# v1_1_Main.net
KiCad netlist of a schematic drawn in EAGLE
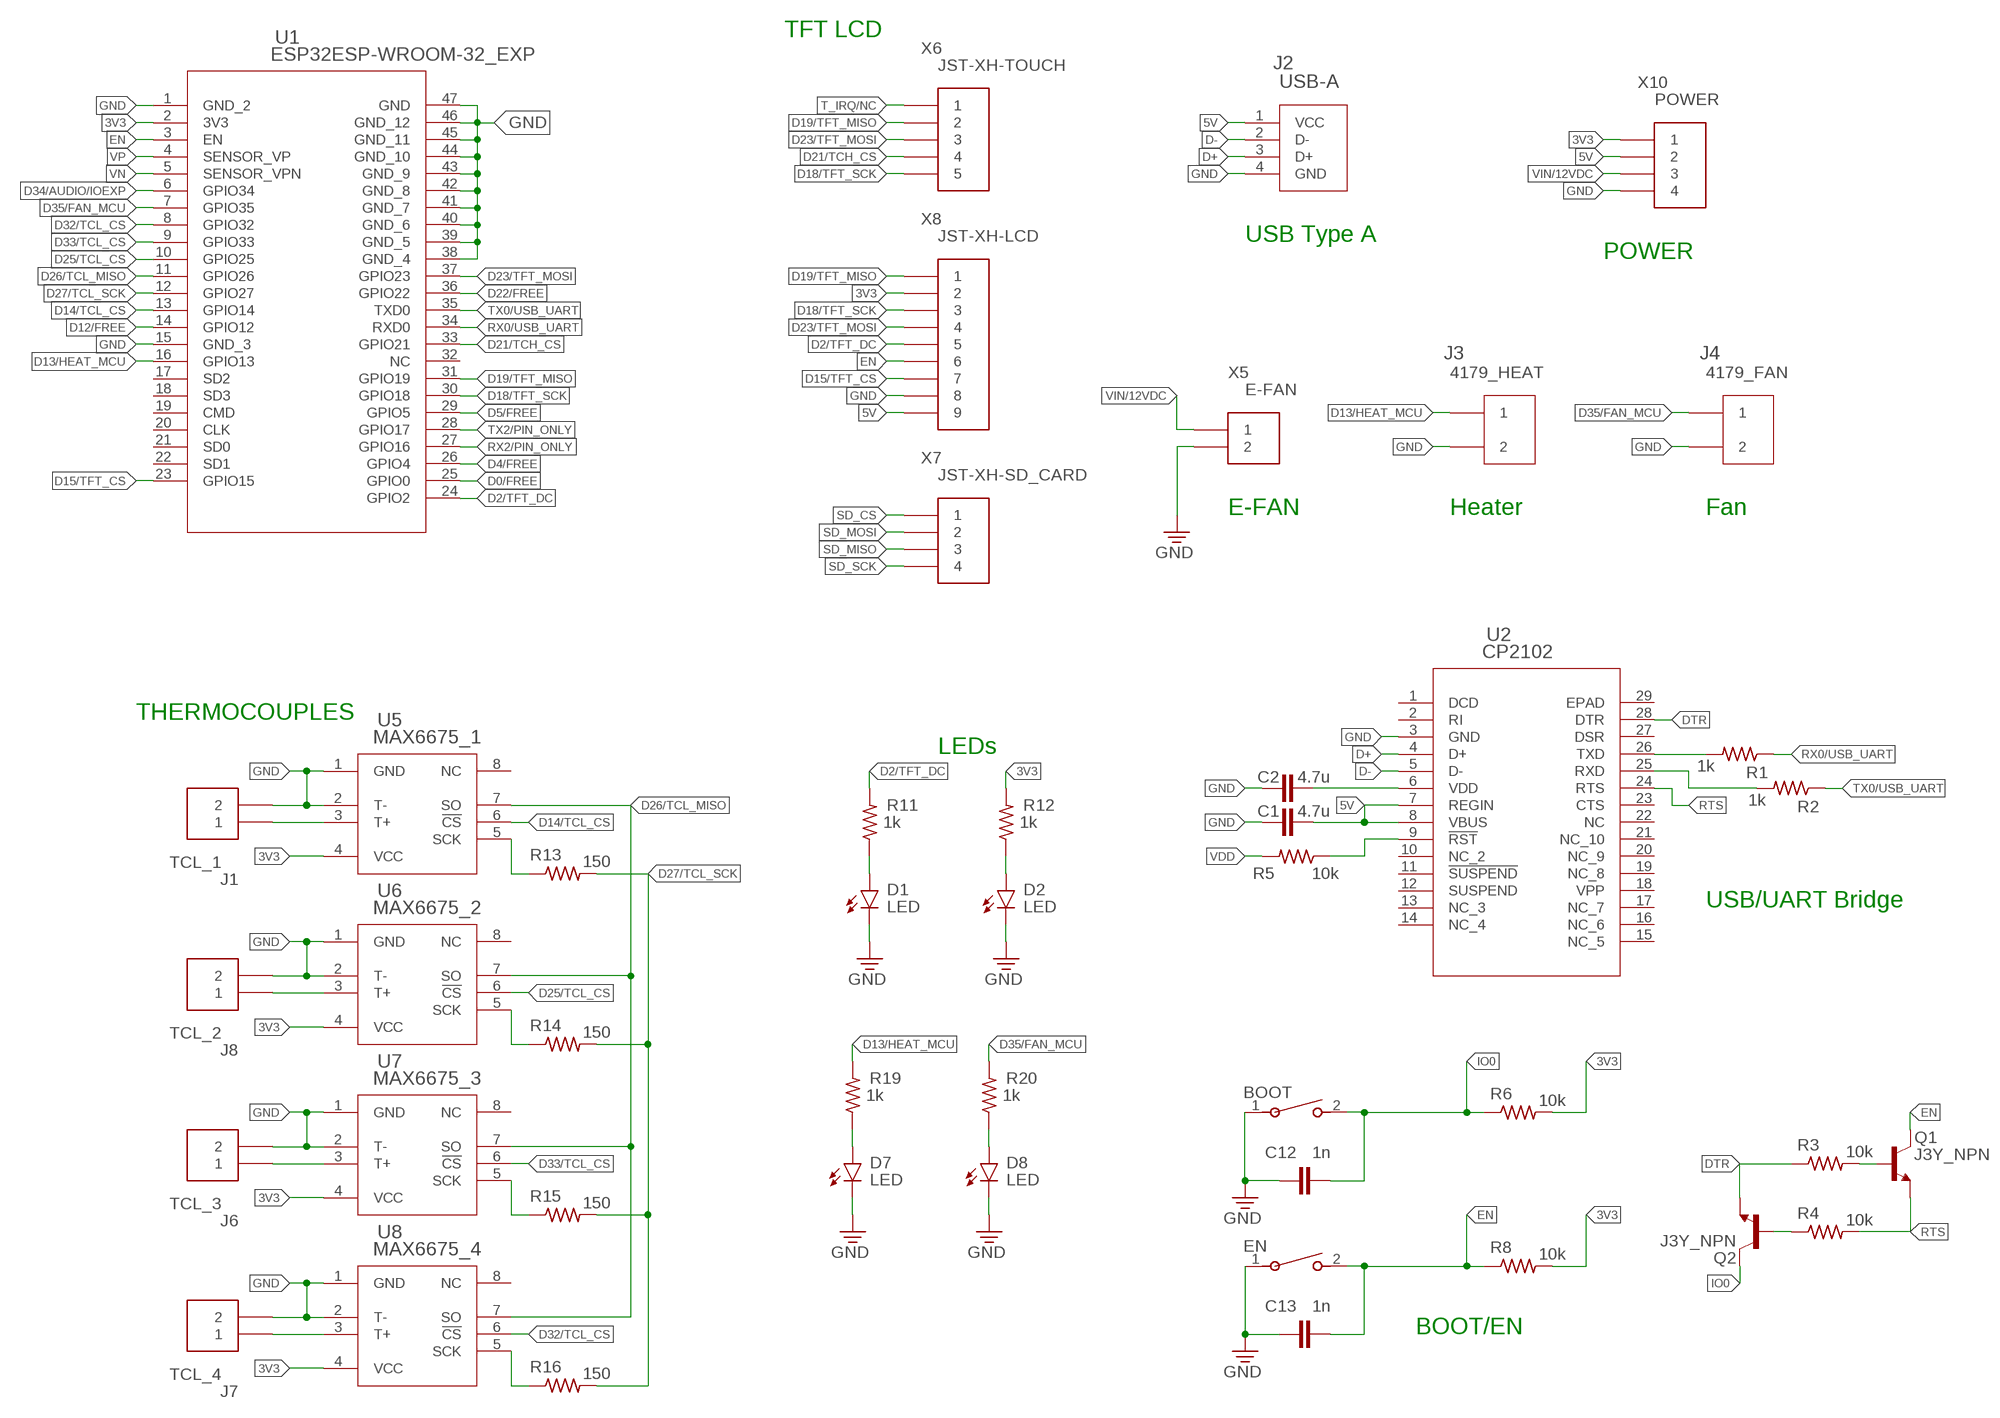
[diagram p0: schematic, sheet 1]

(export (version "E")
  (design (tool "Eeschema 10.0.6"))
  (components
    (comp (ref "BOOT")
      (value "EVQ22705RSW_EVQ22705R_PAN")
      (footprint "eagle-import:SW_EVQ22705R_PAN")
      (fields
        (field (name "MANUFACTURER_PART_NUMBER") "EVQ-22705R")
        (field (name "COPYRIGHT") "Copyright (C) 2024 Ultra Librarian. All rights reserved.")
      )
      (libsource (lib "eagle-import") (part "EVQ22705RSW_EVQ22705R_PAN"))
    )
    (comp (ref "C1")
      (value "4.7u")
      (footprint "eagle-import:CAPC2012X110")
      (libsource (lib "eagle-import") (part "CCHIP-0805(2012-METRIC)_"))
    )
    (comp (ref "C2")
      (value "4.7u")
      (footprint "eagle-import:CAPC2012X110")
      (libsource (lib "eagle-import") (part "CCHIP-0805(2012-METRIC)_"))
    )
    (comp (ref "C12")
      (value "1n")
      (footprint "eagle-import:CAPC2012X110")
      (libsource (lib "eagle-import") (part "CCHIP-0805(2012-METRIC)_"))
    )
    (comp (ref "C13")
      (value "1n")
      (footprint "eagle-import:CAPC2012X110")
      (libsource (lib "eagle-import") (part "CCHIP-0805(2012-METRIC)_"))
    )
    (comp (ref "D1")
      (value "LED")
      (footprint "eagle-import:LEDC2012X110N_FLAT-B")
      (libsource (lib "eagle-import") (part "CHIP-FLAT-B_0805"))
    )
    (comp (ref "D2")
      (value "LED")
      (footprint "eagle-import:LEDC2012X110N_FLAT-B")
      (libsource (lib "eagle-import") (part "CHIP-FLAT-B_0805"))
    )
    (comp (ref "D7")
      (value "LED")
      (footprint "eagle-import:LEDC2012X110N_FLAT-B")
      (libsource (lib "eagle-import") (part "CHIP-FLAT-B_0805"))
    )
    (comp (ref "D8")
      (value "LED")
      (footprint "eagle-import:LEDC2012X110N_FLAT-B")
      (libsource (lib "eagle-import") (part "CHIP-FLAT-B_0805"))
    )
    (comp (ref "EN")
      (value "EVQ22705RSW_EVQ22705R_PAN")
      (footprint "eagle-import:SW_EVQ22705R_PAN")
      (fields
        (field (name "MANUFACTURER_PART_NUMBER") "EVQ-22705R")
        (field (name "COPYRIGHT") "Copyright (C) 2024 Ultra Librarian. All rights reserved.")
      )
      (libsource (lib "eagle-import") (part "EVQ22705RSW_EVQ22705R_PAN"))
    )
    (comp (ref "J1")
      (value "TCL_1")
      (footprint "eagle-import:CONN_OSTVN02A150_OST")
      (fields
        (field (name "MANUFACTURER_PART_NUMBER") "OSTVN02A150")
        (field (name "COPYRIGHT") "Copyright (C) 2025 Ultra Librarian. All rights reserved.")
      )
      (libsource (lib "eagle-import") (part "OSTVN02A150CONN_OSTVN02A150_OST"))
    )
    (comp (ref "J2")
      (value "USB-A")
      (footprint "eagle-import:USB-A")
      (fields
        (field (name "MANUFACTURER_PART_NUMBER") "USB-A1VSB6")
        (field (name "COPYRIGHT") "Copyright (C) 2025 Ultra Librarian. All rights reserved.")
      )
      (libsource (lib "eagle-import") (part "USB-A1VSB6_OST"))
    )
    (comp (ref "J3")
      (value "4179_HEAT")
      (footprint "eagle-import:41791")
      (fields
        (field (name "MANUFACTURER_PART_NUMBER") "417910849")
        (field (name "COPYRIGHT") "Copyright (C) 2025 Ultra Librarian. All rights reserved.")
      )
      (libsource (lib "eagle-import") (part "4179_SDA"))
    )
    (comp (ref "J4")
      (value "4179_FAN")
      (footprint "eagle-import:41791")
      (fields
        (field (name "MANUFACTURER_PART_NUMBER") "417910849")
        (field (name "COPYRIGHT") "Copyright (C) 2025 Ultra Librarian. All rights reserved.")
      )
      (libsource (lib "eagle-import") (part "4179_SDA"))
    )
    (comp (ref "J6")
      (value "TCL_3")
      (footprint "eagle-import:CONN_OSTVN02A150_OST")
      (fields
        (field (name "MANUFACTURER_PART_NUMBER") "OSTVN02A150")
        (field (name "COPYRIGHT") "Copyright (C) 2025 Ultra Librarian. All rights reserved.")
      )
      (libsource (lib "eagle-import") (part "OSTVN02A150CONN_OSTVN02A150_OST"))
    )
    (comp (ref "J7")
      (value "TCL_4")
      (footprint "eagle-import:CONN_OSTVN02A150_OST")
      (fields
        (field (name "MANUFACTURER_PART_NUMBER") "OSTVN02A150")
        (field (name "COPYRIGHT") "Copyright (C) 2025 Ultra Librarian. All rights reserved.")
      )
      (libsource (lib "eagle-import") (part "OSTVN02A150CONN_OSTVN02A150_OST"))
    )
    (comp (ref "J8")
      (value "TCL_2")
      (footprint "eagle-import:CONN_OSTVN02A150_OST")
      (fields
        (field (name "MANUFACTURER_PART_NUMBER") "OSTVN02A150")
        (field (name "COPYRIGHT") "Copyright (C) 2025 Ultra Librarian. All rights reserved.")
      )
      (libsource (lib "eagle-import") (part "OSTVN02A150CONN_OSTVN02A150_OST"))
    )
    (comp (ref "Q1")
      (value "J3Y_NPN")
      (footprint "eagle-import:SC59")
      (libsource (lib "eagle-import") (part "NPNSC59-BEC_"))
    )
    (comp (ref "Q2")
      (value "J3Y_NPN")
      (footprint "eagle-import:SC59")
      (libsource (lib "eagle-import") (part "NPNSC59-BEC_"))
    )
    (comp (ref "R1")
      (value "1k")
      (footprint "eagle-import:RESC2012X65")
      (libsource (lib "eagle-import") (part "R-USCHIP-0805(2012-METRIC)_"))
    )
    (comp (ref "R2")
      (value "1k")
      (footprint "eagle-import:RESC2012X65")
      (libsource (lib "eagle-import") (part "R-USCHIP-0805(2012-METRIC)_"))
    )
    (comp (ref "R3")
      (value "10k")
      (footprint "eagle-import:RESC2012X65")
      (libsource (lib "eagle-import") (part "R-USCHIP-0805(2012-METRIC)_"))
    )
    (comp (ref "R4")
      (value "10k")
      (footprint "eagle-import:RESC2012X65")
      (libsource (lib "eagle-import") (part "R-USCHIP-0805(2012-METRIC)_"))
    )
    (comp (ref "R5")
      (value "10k")
      (footprint "eagle-import:RESC2012X65")
      (libsource (lib "eagle-import") (part "R-USCHIP-0805(2012-METRIC)_"))
    )
    (comp (ref "R6")
      (value "10k")
      (footprint "eagle-import:RESC2012X65")
      (libsource (lib "eagle-import") (part "R-USCHIP-0805(2012-METRIC)_"))
    )
    (comp (ref "R8")
      (value "10k")
      (footprint "eagle-import:RESC2012X65")
      (libsource (lib "eagle-import") (part "R-USCHIP-0805(2012-METRIC)_"))
    )
    (comp (ref "R11")
      (value "1k")
      (footprint "eagle-import:RESC2012X65")
      (libsource (lib "eagle-import") (part "R-USCHIP-0805(2012-METRIC)_"))
    )
    (comp (ref "R12")
      (value "1k")
      (footprint "eagle-import:RESC2012X65")
      (libsource (lib "eagle-import") (part "R-USCHIP-0805(2012-METRIC)_"))
    )
    (comp (ref "R13")
      (value "150")
      (footprint "eagle-import:RESC2012X65")
      (libsource (lib "eagle-import") (part "R-USCHIP-0805(2012-METRIC)_"))
    )
    (comp (ref "R14")
      (value "150")
      (footprint "eagle-import:RESC2012X65")
      (libsource (lib "eagle-import") (part "R-USCHIP-0805(2012-METRIC)_"))
    )
    (comp (ref "R15")
      (value "150")
      (footprint "eagle-import:RESC2012X65")
      (libsource (lib "eagle-import") (part "R-USCHIP-0805(2012-METRIC)_"))
    )
    (comp (ref "R16")
      (value "150")
      (footprint "eagle-import:RESC2012X65")
      (libsource (lib "eagle-import") (part "R-USCHIP-0805(2012-METRIC)_"))
    )
    (comp (ref "R19")
      (value "1k")
      (footprint "eagle-import:RESC2012X65")
      (libsource (lib "eagle-import") (part "R-USCHIP-0805(2012-METRIC)_"))
    )
    (comp (ref "R20")
      (value "1k")
      (footprint "eagle-import:RESC2012X65")
      (libsource (lib "eagle-import") (part "R-USCHIP-0805(2012-METRIC)_"))
    )
    (comp (ref "U1")
      (value "ESP32ESP-WROOM-32_EXP")
      (footprint "eagle-import:ESP32_SCH_PCB")
      (fields
        (field (name "MANUFACTURER_PART_NUMBER") "ESP-WROOM-32")
        (field (name "COPYRIGHT") "Copyright (C) 2024 Ultra Librarian. All rights reserved.")
      )
      (libsource (lib "eagle-import") (part "ESP32ESP-WROOM-32_EXP"))
    )
    (comp (ref "U2")
      (value "CP2102")
      (footprint "eagle-import:QFN28_5X5_SIL")
      (fields
        (field (name "MANUFACTURER_PART_NUMBER") "CP2102-GM")
        (field (name "COPYRIGHT") "Copyright (C) 2025 Ultra Librarian. All rights reserved.")
      )
      (libsource (lib "eagle-import") (part "CP2102-GMQFN28_5X5_SIL"))
    )
    (comp (ref "U5")
      (value "MAX6675_1")
      (footprint "eagle-import:_ISA_MXM")
      (fields
        (field (name "MANUFACTURER_PART_NUMBER") "MAX6675ISA+")
        (field (name "COPYRIGHT") "Copyright (C) 2025 Ultra Librarian. All rights reserved.")
      )
      (libsource (lib "eagle-import") (part "MAX6675_ISA_MXM"))
    )
    (comp (ref "U6")
      (value "MAX6675_2")
      (footprint "eagle-import:_ISA_MXM")
      (fields
        (field (name "MANUFACTURER_PART_NUMBER") "MAX6675ISA+")
        (field (name "COPYRIGHT") "Copyright (C) 2025 Ultra Librarian. All rights reserved.")
      )
      (libsource (lib "eagle-import") (part "MAX6675_ISA_MXM"))
    )
    (comp (ref "U7")
      (value "MAX6675_3")
      (footprint "eagle-import:_ISA_MXM")
      (fields
        (field (name "MANUFACTURER_PART_NUMBER") "MAX6675ISA+")
        (field (name "COPYRIGHT") "Copyright (C) 2025 Ultra Librarian. All rights reserved.")
      )
      (libsource (lib "eagle-import") (part "MAX6675_ISA_MXM"))
    )
    (comp (ref "U8")
      (value "MAX6675_4")
      (footprint "eagle-import:_ISA_MXM")
      (fields
        (field (name "MANUFACTURER_PART_NUMBER") "MAX6675ISA+")
        (field (name "COPYRIGHT") "Copyright (C) 2025 Ultra Librarian. All rights reserved.")
      )
      (libsource (lib "eagle-import") (part "MAX6675_ISA_MXM"))
    )
    (comp (ref "X5")
      (value "E-FAN")
      (footprint "eagle-import:-LONG-PAD")
      (libsource (lib "eagle-import") (part "JST-XH-02-PIN-LONG-PAD"))
    )
    (comp (ref "X6")
      (value "JST-XH-TOUCH")
      (footprint "eagle-import:JST-XH-05-PACKAGE-LONG-PAD")
      (libsource (lib "eagle-import") (part "JST-XH-05-PIN-LONG-PAD"))
    )
    (comp (ref "X7")
      (value "JST-XH-SD_CARD")
      (footprint "eagle-import:JST-XH-04-PACKAGE-LONG-PAD")
      (libsource (lib "eagle-import") (part "JST-XH-04-PIN-LONG-PAD"))
    )
    (comp (ref "X8")
      (value "JST-XH-LCD")
      (footprint "eagle-import:JST-XH-09-PACKAGE-LONG-PAD")
      (libsource (lib "eagle-import") (part "JST-XH-09-PIN-LONG-PAD"))
    )
    (comp (ref "X10")
      (value "POWER")
      (footprint "eagle-import:JST-XH-04-PACKAGE-LONG-PAD")
      (libsource (lib "eagle-import") (part "JST-XH-04-PIN-LONG-PAD"))
    )
  )
  (nets
    (net (code "1") (name "3V3") (class "Default")
      (node (ref "R12") (pin "2") (pinfunction "2_2") (pintype "passive"))
      (node (ref "R6") (pin "2") (pinfunction "2_2") (pintype "passive"))
      (node (ref "R8") (pin "2") (pinfunction "2_2") (pintype "passive"))
      (node (ref "U1") (pin "2") (pinfunction "3V3_2") (pintype "power_in"))
      (node (ref "U5") (pin "4") (pinfunction "VCC_4") (pintype "power_in"))
      (node (ref "U6") (pin "4") (pinfunction "VCC_4") (pintype "power_in"))
      (node (ref "U7") (pin "4") (pinfunction "VCC_4") (pintype "power_in"))
      (node (ref "U8") (pin "4") (pinfunction "VCC_4") (pintype "power_in"))
      (node (ref "X10") (pin "1") (pinfunction "1_1") (pintype "passive"))
      (node (ref "X8") (pin "2") (pinfunction "2_2") (pintype "passive"))
    )
    (net (code "2") (name "5V") (class "Default")
      (node (ref "C1") (pin "2") (pinfunction "2_2") (pintype "passive"))
      (node (ref "J2") (pin "1") (pinfunction "VCC_1") (pintype "passive"))
      (node (ref "U2") (pin "7") (pinfunction "REGIN_7") (pintype "input"))
      (node (ref "U2") (pin "8") (pinfunction "VBUS_8") (pintype "input"))
      (node (ref "X10") (pin "2") (pinfunction "2_2") (pintype "passive"))
      (node (ref "X8") (pin "9") (pinfunction "9_9") (pintype "passive"))
    )
    (net (code "3") (name "D+") (class "Default")
      (node (ref "J2") (pin "3") (pinfunction "D+_3") (pintype "passive"))
      (node (ref "U2") (pin "4") (pinfunction "D+_4") (pintype "bidirectional"))
    )
    (net (code "4") (name "D-") (class "Default")
      (node (ref "J2") (pin "2") (pinfunction "D-_2") (pintype "passive"))
      (node (ref "U2") (pin "5") (pinfunction "D-_5") (pintype "bidirectional"))
    )
    (net (code "5") (name "D0{slash}FREE") (class "Default")
      (node (ref "U1") (pin "25") (pinfunction "GPIO0_25") (pintype "bidirectional"))
    )
    (net (code "6") (name "D2{slash}TFT_DC") (class "Default")
      (node (ref "R11") (pin "2") (pinfunction "2_2") (pintype "passive"))
      (node (ref "U1") (pin "24") (pinfunction "GPIO2_24") (pintype "bidirectional"))
      (node (ref "X8") (pin "5") (pinfunction "5_5") (pintype "passive"))
    )
    (net (code "7") (name "D4{slash}FREE") (class "Default")
      (node (ref "U1") (pin "26") (pinfunction "GPIO4_26") (pintype "bidirectional"))
    )
    (net (code "8") (name "D5{slash}FREE") (class "Default")
      (node (ref "U1") (pin "29") (pinfunction "GPIO5_29") (pintype "bidirectional"))
    )
    (net (code "9") (name "D12{slash}FREE") (class "Default")
      (node (ref "U1") (pin "14") (pinfunction "GPIO12_14") (pintype "bidirectional"))
    )
    (net (code "10") (name "D13{slash}HEAT_MCU") (class "Default")
      (node (ref "J3") (pin "1") (pinfunction "1_1") (pintype "passive"))
      (node (ref "R19") (pin "2") (pinfunction "2_2") (pintype "passive"))
      (node (ref "U1") (pin "16") (pinfunction "GPIO13_16") (pintype "bidirectional"))
    )
    (net (code "11") (name "D14{slash}TCL_CS") (class "Default")
      (node (ref "U1") (pin "13") (pinfunction "GPIO14_13") (pintype "bidirectional"))
      (node (ref "U5") (pin "6") (pinfunction "~{CS}_6") (pintype "input"))
    )
    (net (code "12") (name "D15{slash}TFT_CS") (class "Default")
      (node (ref "U1") (pin "23") (pinfunction "GPIO15_23") (pintype "bidirectional"))
      (node (ref "X8") (pin "7") (pinfunction "7_7") (pintype "passive"))
    )
    (net (code "13") (name "D18{slash}TFT_SCK") (class "Default")
      (node (ref "U1") (pin "30") (pinfunction "GPIO18_30") (pintype "bidirectional"))
      (node (ref "X6") (pin "5") (pinfunction "5_5") (pintype "passive"))
      (node (ref "X8") (pin "3") (pinfunction "3_3") (pintype "passive"))
    )
    (net (code "14") (name "D19{slash}TFT_MISO") (class "Default")
      (node (ref "U1") (pin "31") (pinfunction "GPIO19_31") (pintype "bidirectional"))
      (node (ref "X6") (pin "2") (pinfunction "2_2") (pintype "passive"))
      (node (ref "X8") (pin "1") (pinfunction "1_1") (pintype "passive"))
    )
    (net (code "15") (name "D21{slash}TCH_CS") (class "Default")
      (node (ref "U1") (pin "33") (pinfunction "GPIO21_33") (pintype "bidirectional"))
      (node (ref "X6") (pin "4") (pinfunction "4_4") (pintype "passive"))
    )
    (net (code "16") (name "D22{slash}FREE") (class "Default")
      (node (ref "U1") (pin "36") (pinfunction "GPIO22_36") (pintype "bidirectional"))
    )
    (net (code "17") (name "D23{slash}TFT_MOSI") (class "Default")
      (node (ref "U1") (pin "37") (pinfunction "GPIO23_37") (pintype "bidirectional"))
      (node (ref "X6") (pin "3") (pinfunction "3_3") (pintype "passive"))
      (node (ref "X8") (pin "4") (pinfunction "4_4") (pintype "passive"))
    )
    (net (code "18") (name "D25{slash}TCL_CS") (class "Default")
      (node (ref "U1") (pin "10") (pinfunction "GPIO25_10") (pintype "bidirectional"))
      (node (ref "U6") (pin "6") (pinfunction "~{CS}_6") (pintype "input"))
    )
    (net (code "19") (name "D26{slash}TCL_MISO") (class "Default")
      (node (ref "U1") (pin "11") (pinfunction "GPIO26_11") (pintype "bidirectional"))
      (node (ref "U5") (pin "7") (pinfunction "SO_7") (pintype "output"))
      (node (ref "U6") (pin "7") (pinfunction "SO_7") (pintype "output"))
      (node (ref "U7") (pin "7") (pinfunction "SO_7") (pintype "output"))
      (node (ref "U8") (pin "7") (pinfunction "SO_7") (pintype "output"))
    )
    (net (code "20") (name "D27{slash}TCL_SCK") (class "Default")
      (node (ref "R13") (pin "2") (pinfunction "2_2") (pintype "passive"))
      (node (ref "R14") (pin "2") (pinfunction "2_2") (pintype "passive"))
      (node (ref "R15") (pin "2") (pinfunction "2_2") (pintype "passive"))
      (node (ref "R16") (pin "2") (pinfunction "2_2") (pintype "passive"))
      (node (ref "U1") (pin "12") (pinfunction "GPIO27_12") (pintype "bidirectional"))
    )
    (net (code "21") (name "D32{slash}TCL_CS") (class "Default")
      (node (ref "U1") (pin "8") (pinfunction "GPIO32_8") (pintype "bidirectional"))
      (node (ref "U8") (pin "6") (pinfunction "~{CS}_6") (pintype "input"))
    )
    (net (code "22") (name "D33{slash}TCL_CS") (class "Default")
      (node (ref "U1") (pin "9") (pinfunction "GPIO33_9") (pintype "bidirectional"))
      (node (ref "U7") (pin "6") (pinfunction "~{CS}_6") (pintype "input"))
    )
    (net (code "23") (name "D34{slash}AUDIO{slash}IOEXP") (class "Default")
      (node (ref "U1") (pin "6") (pinfunction "GPIO34_6") (pintype "input"))
    )
    (net (code "24") (name "D35{slash}FAN_MCU") (class "Default")
      (node (ref "J4") (pin "1") (pinfunction "1_1") (pintype "passive"))
      (node (ref "R20") (pin "2") (pinfunction "2_2") (pintype "passive"))
      (node (ref "U1") (pin "7") (pinfunction "GPIO35_7") (pintype "input"))
    )
    (net (code "25") (name "DTR") (class "Default")
      (node (ref "Q2") (pin "E") (pinfunction "E_E") (pintype "passive"))
      (node (ref "R3") (pin "1") (pinfunction "1_1") (pintype "passive"))
      (node (ref "U2") (pin "28") (pinfunction "DTR_28") (pintype "output"))
    )
    (net (code "26") (name "EN") (class "Default")
      (node (ref "C13") (pin "2") (pinfunction "2_2") (pintype "passive"))
      (node (ref "EN") (pin "2") (pinfunction "2_2") (pintype "passive"))
      (node (ref "Q1") (pin "C") (pinfunction "C_C") (pintype "passive"))
      (node (ref "R8") (pin "1") (pinfunction "1_1") (pintype "passive"))
      (node (ref "U1") (pin "3") (pinfunction "EN_3") (pintype "input"))
      (node (ref "X8") (pin "6") (pinfunction "6_6") (pintype "passive"))
    )
    (net (code "27") (name "GND") (class "Default")
      (node (ref "BOOT") (pin "1") (pinfunction "1_1") (pintype "passive"))
      (node (ref "C1") (pin "1") (pinfunction "1_1") (pintype "passive"))
      (node (ref "C12") (pin "1") (pinfunction "1_1") (pintype "passive"))
      (node (ref "C13") (pin "1") (pinfunction "1_1") (pintype "passive"))
      (node (ref "C2") (pin "1") (pinfunction "1_1") (pintype "passive"))
      (node (ref "D1") (pin "C") (pinfunction "C_C") (pintype "passive"))
      (node (ref "D2") (pin "C") (pinfunction "C_C") (pintype "passive"))
      (node (ref "D7") (pin "C") (pinfunction "C_C") (pintype "passive"))
      (node (ref "D8") (pin "C") (pinfunction "C_C") (pintype "passive"))
      (node (ref "EN") (pin "1") (pinfunction "1_1") (pintype "passive"))
      (node (ref "J1") (pin "2") (pinfunction "2_2") (pintype "passive"))
      (node (ref "J2") (pin "4") (pinfunction "GND_4") (pintype "passive"))
      (node (ref "J3") (pin "2") (pinfunction "2_2") (pintype "passive"))
      (node (ref "J4") (pin "2") (pinfunction "2_2") (pintype "passive"))
      (node (ref "J6") (pin "2") (pinfunction "2_2") (pintype "passive"))
      (node (ref "J7") (pin "2") (pinfunction "2_2") (pintype "passive"))
      (node (ref "J8") (pin "2") (pinfunction "2_2") (pintype "passive"))
      (node (ref "U1") (pin "1") (pinfunction "GND_2_1") (pintype "passive"))
      (node (ref "U1") (pin "15") (pinfunction "GND_3_15") (pintype "passive"))
      (node (ref "U1") (pin "38") (pinfunction "GND_4_38") (pintype "passive"))
      (node (ref "U1") (pin "39") (pinfunction "GND_5_39") (pintype "passive"))
      (node (ref "U1") (pin "40") (pinfunction "GND_6_40") (pintype "passive"))
      (node (ref "U1") (pin "41") (pinfunction "GND_7_41") (pintype "passive"))
      (node (ref "U1") (pin "42") (pinfunction "GND_8_42") (pintype "passive"))
      (node (ref "U1") (pin "43") (pinfunction "GND_9_43") (pintype "passive"))
      (node (ref "U1") (pin "44") (pinfunction "GND_10_44") (pintype "passive"))
      (node (ref "U1") (pin "45") (pinfunction "GND_11_45") (pintype "passive"))
      (node (ref "U1") (pin "46") (pinfunction "GND_12_46") (pintype "passive"))
      (node (ref "U1") (pin "47") (pinfunction "GND_47") (pintype "passive"))
      (node (ref "U2") (pin "3") (pinfunction "GND_3") (pintype "power_in"))
      (node (ref "U5") (pin "1") (pinfunction "GND_1") (pintype "power_in"))
      (node (ref "U5") (pin "2") (pinfunction "T-_2") (pintype "passive"))
      (node (ref "U6") (pin "1") (pinfunction "GND_1") (pintype "power_in"))
      (node (ref "U6") (pin "2") (pinfunction "T-_2") (pintype "passive"))
      (node (ref "U7") (pin "1") (pinfunction "GND_1") (pintype "power_in"))
      (node (ref "U7") (pin "2") (pinfunction "T-_2") (pintype "passive"))
      (node (ref "U8") (pin "1") (pinfunction "GND_1") (pintype "power_in"))
      (node (ref "U8") (pin "2") (pinfunction "T-_2") (pintype "passive"))
      (node (ref "X10") (pin "4") (pinfunction "4_4") (pintype "passive"))
      (node (ref "X5") (pin "2") (pinfunction "2_2") (pintype "passive"))
      (node (ref "X8") (pin "8") (pinfunction "8_8") (pintype "passive"))
    )
    (net (code "28") (name "IO0") (class "Default")
      (node (ref "BOOT") (pin "2") (pinfunction "2_2") (pintype "passive"))
      (node (ref "C12") (pin "2") (pinfunction "2_2") (pintype "passive"))
      (node (ref "Q2") (pin "C") (pinfunction "C_C") (pintype "passive"))
      (node (ref "R6") (pin "1") (pinfunction "1_1") (pintype "passive"))
    )
    (net (code "29") (name "Net-(D1-PadA)") (class "Default")
      (node (ref "D1") (pin "A") (pinfunction "A_A") (pintype "passive"))
      (node (ref "R11") (pin "1") (pinfunction "1_1") (pintype "passive"))
    )
    (net (code "30") (name "Net-(D2-PadA)") (class "Default")
      (node (ref "D2") (pin "A") (pinfunction "A_A") (pintype "passive"))
      (node (ref "R12") (pin "1") (pinfunction "1_1") (pintype "passive"))
    )
    (net (code "31") (name "Net-(D7-PadA)") (class "Default")
      (node (ref "D7") (pin "A") (pinfunction "A_A") (pintype "passive"))
      (node (ref "R19") (pin "1") (pinfunction "1_1") (pintype "passive"))
    )
    (net (code "32") (name "Net-(D8-PadA)") (class "Default")
      (node (ref "D8") (pin "A") (pinfunction "A_A") (pintype "passive"))
      (node (ref "R20") (pin "1") (pinfunction "1_1") (pintype "passive"))
    )
    (net (code "33") (name "Net-(Q1-PadB)") (class "Default")
      (node (ref "Q1") (pin "B") (pinfunction "B_B") (pintype "passive"))
      (node (ref "R3") (pin "2") (pinfunction "2_2") (pintype "passive"))
    )
    (net (code "34") (name "Net-(Q2-PadB)") (class "Default")
      (node (ref "Q2") (pin "B") (pinfunction "B_B") (pintype "passive"))
      (node (ref "R4") (pin "1") (pinfunction "1_1") (pintype "passive"))
    )
    (net (code "35") (name "Net-(U2-RXD)") (class "Default")
      (node (ref "R2") (pin "2") (pinfunction "2_2") (pintype "passive"))
      (node (ref "U2") (pin "25") (pinfunction "RXD_25") (pintype "input"))
    )
    (net (code "36") (name "Net-(U2-TXD)") (class "Default")
      (node (ref "R1") (pin "2") (pinfunction "2_2") (pintype "passive"))
      (node (ref "U2") (pin "26") (pinfunction "TXD_26") (pintype "output"))
    )
    (net (code "37") (name "Net-(U2-~{RST})") (class "Default")
      (node (ref "R5") (pin "1") (pinfunction "1_1") (pintype "passive"))
      (node (ref "U2") (pin "9") (pinfunction "~{RST}_9") (pintype "bidirectional"))
    )
    (net (code "38") (name "Net-(U5-SCK)") (class "Default")
      (node (ref "R13") (pin "1") (pinfunction "1_1") (pintype "passive"))
      (node (ref "U5") (pin "5") (pinfunction "SCK_5") (pintype "input"))
    )
    (net (code "39") (name "Net-(U5-T+)") (class "Default")
      (node (ref "J1") (pin "1") (pinfunction "1_1") (pintype "passive"))
      (node (ref "U5") (pin "3") (pinfunction "T+_3") (pintype "passive"))
    )
    (net (code "40") (name "Net-(U6-SCK)") (class "Default")
      (node (ref "R14") (pin "1") (pinfunction "1_1") (pintype "passive"))
      (node (ref "U6") (pin "5") (pinfunction "SCK_5") (pintype "input"))
    )
    (net (code "41") (name "Net-(U6-T+)") (class "Default")
      (node (ref "J8") (pin "1") (pinfunction "1_1") (pintype "passive"))
      (node (ref "U6") (pin "3") (pinfunction "T+_3") (pintype "passive"))
    )
    (net (code "42") (name "Net-(U7-SCK)") (class "Default")
      (node (ref "R15") (pin "1") (pinfunction "1_1") (pintype "passive"))
      (node (ref "U7") (pin "5") (pinfunction "SCK_5") (pintype "input"))
    )
    (net (code "43") (name "Net-(U7-T+)") (class "Default")
      (node (ref "J6") (pin "1") (pinfunction "1_1") (pintype "passive"))
      (node (ref "U7") (pin "3") (pinfunction "T+_3") (pintype "passive"))
    )
    (net (code "44") (name "Net-(U8-SCK)") (class "Default")
      (node (ref "R16") (pin "1") (pinfunction "1_1") (pintype "passive"))
      (node (ref "U8") (pin "5") (pinfunction "SCK_5") (pintype "input"))
    )
    (net (code "45") (name "Net-(U8-T+)") (class "Default")
      (node (ref "J7") (pin "1") (pinfunction "1_1") (pintype "passive"))
      (node (ref "U8") (pin "3") (pinfunction "T+_3") (pintype "passive"))
    )
    (net (code "46") (name "RTS") (class "Default")
      (node (ref "Q1") (pin "E") (pinfunction "E_E") (pintype "passive"))
      (node (ref "R4") (pin "2") (pinfunction "2_2") (pintype "passive"))
      (node (ref "U2") (pin "24") (pinfunction "RTS_24") (pintype "output"))
    )
    (net (code "47") (name "RX0{slash}USB_UART") (class "Default")
      (node (ref "R1") (pin "1") (pinfunction "1_1") (pintype "passive"))
      (node (ref "U1") (pin "34") (pinfunction "RXD0_34") (pintype "bidirectional"))
    )
    (net (code "48") (name "RX2{slash}PIN_ONLY") (class "Default")
      (node (ref "U1") (pin "27") (pinfunction "GPIO16_27") (pintype "bidirectional"))
    )
    (net (code "49") (name "SD_CS") (class "Default")
      (node (ref "X7") (pin "1") (pinfunction "1_1") (pintype "passive"))
    )
    (net (code "50") (name "SD_MISO") (class "Default")
      (node (ref "X7") (pin "3") (pinfunction "3_3") (pintype "passive"))
    )
    (net (code "51") (name "SD_MOSI") (class "Default")
      (node (ref "X7") (pin "2") (pinfunction "2_2") (pintype "passive"))
    )
    (net (code "52") (name "SD_SCK") (class "Default")
      (node (ref "X7") (pin "4") (pinfunction "4_4") (pintype "passive"))
    )
    (net (code "53") (name "TX0{slash}USB_UART") (class "Default")
      (node (ref "R2") (pin "1") (pinfunction "1_1") (pintype "passive"))
      (node (ref "U1") (pin "35") (pinfunction "TXD0_35") (pintype "bidirectional"))
    )
    (net (code "54") (name "TX2{slash}PIN_ONLY") (class "Default")
      (node (ref "U1") (pin "28") (pinfunction "GPIO17_28") (pintype "bidirectional"))
    )
    (net (code "55") (name "T_IRQ{slash}NC") (class "Default")
      (node (ref "X6") (pin "1") (pinfunction "1_1") (pintype "passive"))
    )
    (net (code "56") (name "VDD") (class "Default")
      (node (ref "C2") (pin "2") (pinfunction "2_2") (pintype "passive"))
      (node (ref "R5") (pin "2") (pinfunction "2_2") (pintype "passive"))
      (node (ref "U2") (pin "6") (pinfunction "VDD_6") (pintype "power_in"))
    )
    (net (code "57") (name "VIN{slash}12VDC") (class "Default")
      (node (ref "X10") (pin "3") (pinfunction "3_3") (pintype "passive"))
      (node (ref "X5") (pin "1") (pinfunction "1_1") (pintype "passive"))
    )
    (net (code "58") (name "VN") (class "Default")
      (node (ref "U1") (pin "5") (pinfunction "SENSOR_VPN_5") (pintype "input"))
    )
    (net (code "59") (name "VP") (class "Default")
      (node (ref "U1") (pin "4") (pinfunction "SENSOR_VP_4") (pintype "input"))
    )
    (net (code "60") (name "unconnected-(U1-CLK-Pad20)") (class "Default")
      (node (ref "U1") (pin "20") (pinfunction "CLK_20") (pintype "no_connect"))
    )
    (net (code "61") (name "unconnected-(U1-CMD-Pad19)") (class "Default")
      (node (ref "U1") (pin "19") (pinfunction "CMD_19") (pintype "no_connect"))
    )
    (net (code "62") (name "unconnected-(U1-NC-Pad32)") (class "Default")
      (node (ref "U1") (pin "32") (pinfunction "NC_32") (pintype "no_connect"))
    )
    (net (code "63") (name "unconnected-(U1-SD0-Pad21)") (class "Default")
      (node (ref "U1") (pin "21") (pinfunction "SD0_21") (pintype "no_connect"))
    )
    (net (code "64") (name "unconnected-(U1-SD1-Pad22)") (class "Default")
      (node (ref "U1") (pin "22") (pinfunction "SD1_22") (pintype "no_connect"))
    )
    (net (code "65") (name "unconnected-(U1-SD2-Pad17)") (class "Default")
      (node (ref "U1") (pin "17") (pinfunction "SD2_17") (pintype "no_connect"))
    )
    (net (code "66") (name "unconnected-(U1-SD3-Pad18)") (class "Default")
      (node (ref "U1") (pin "18") (pinfunction "SD3_18") (pintype "no_connect"))
    )
    (net (code "67") (name "unconnected-(U2-CTS-Pad23)") (class "Default")
      (node (ref "U2") (pin "23") (pinfunction "CTS_23") (pintype "no_connect"))
    )
    (net (code "68") (name "unconnected-(U2-DCD-Pad1)") (class "Default")
      (node (ref "U2") (pin "1") (pinfunction "DCD_1") (pintype "no_connect"))
    )
    (net (code "69") (name "unconnected-(U2-DSR-Pad27)") (class "Default")
      (node (ref "U2") (pin "27") (pinfunction "DSR_27") (pintype "no_connect"))
    )
    (net (code "70") (name "unconnected-(U2-EPAD-Pad29)") (class "Default")
      (node (ref "U2") (pin "29") (pinfunction "EPAD_29") (pintype "no_connect"))
    )
    (net (code "71") (name "unconnected-(U2-NC-Pad22)") (class "Default")
      (node (ref "U2") (pin "22") (pinfunction "NC_22") (pintype "no_connect"))
    )
    (net (code "72") (name "unconnected-(U2-NC_2-Pad10)") (class "Default")
      (node (ref "U2") (pin "10") (pinfunction "NC_2_10") (pintype "no_connect"))
    )
    (net (code "73") (name "unconnected-(U2-NC_3-Pad13)") (class "Default")
      (node (ref "U2") (pin "13") (pinfunction "NC_3_13") (pintype "no_connect"))
    )
    (net (code "74") (name "unconnected-(U2-NC_4-Pad14)") (class "Default")
      (node (ref "U2") (pin "14") (pinfunction "NC_4_14") (pintype "no_connect"))
    )
    (net (code "75") (name "unconnected-(U2-NC_5-Pad15)") (class "Default")
      (node (ref "U2") (pin "15") (pinfunction "NC_5_15") (pintype "no_connect"))
    )
    (net (code "76") (name "unconnected-(U2-NC_6-Pad16)") (class "Default")
      (node (ref "U2") (pin "16") (pinfunction "NC_6_16") (pintype "no_connect"))
    )
    (net (code "77") (name "unconnected-(U2-NC_7-Pad17)") (class "Default")
      (node (ref "U2") (pin "17") (pinfunction "NC_7_17") (pintype "no_connect"))
    )
    (net (code "78") (name "unconnected-(U2-NC_8-Pad19)") (class "Default")
      (node (ref "U2") (pin "19") (pinfunction "NC_8_19") (pintype "no_connect"))
    )
    (net (code "79") (name "unconnected-(U2-NC_9-Pad20)") (class "Default")
      (node (ref "U2") (pin "20") (pinfunction "NC_9_20") (pintype "no_connect"))
    )
    (net (code "80") (name "unconnected-(U2-NC_10-Pad21)") (class "Default")
      (node (ref "U2") (pin "21") (pinfunction "NC_10_21") (pintype "no_connect"))
    )
    (net (code "81") (name "unconnected-(U2-RI-Pad2)") (class "Default")
      (node (ref "U2") (pin "2") (pinfunction "RI_2") (pintype "no_connect"))
    )
    (net (code "82") (name "unconnected-(U2-SUSPEND-Pad12)") (class "Default")
      (node (ref "U2") (pin "12") (pinfunction "SUSPEND_12") (pintype "no_connect"))
    )
    (net (code "83") (name "unconnected-(U2-VPP-Pad18)") (class "Default")
      (node (ref "U2") (pin "18") (pinfunction "VPP_18") (pintype "no_connect"))
    )
    (net (code "84") (name "unconnected-(U2-~{SUSPEND}-Pad11)") (class "Default")
      (node (ref "U2") (pin "11") (pinfunction "~{SUSPEND}_11") (pintype "no_connect"))
    )
    (net (code "85") (name "unconnected-(U5-NC-Pad8)") (class "Default")
      (node (ref "U5") (pin "8") (pinfunction "NC_8") (pintype "no_connect"))
    )
    (net (code "86") (name "unconnected-(U6-NC-Pad8)") (class "Default")
      (node (ref "U6") (pin "8") (pinfunction "NC_8") (pintype "no_connect"))
    )
    (net (code "87") (name "unconnected-(U7-NC-Pad8)") (class "Default")
      (node (ref "U7") (pin "8") (pinfunction "NC_8") (pintype "no_connect"))
    )
    (net (code "88") (name "unconnected-(U8-NC-Pad8)") (class "Default")
      (node (ref "U8") (pin "8") (pinfunction "NC_8") (pintype "no_connect"))
    )
  )
)
